# rgb-secamfm500.net
KiCad netlist of a schematic drawn in EAGLE
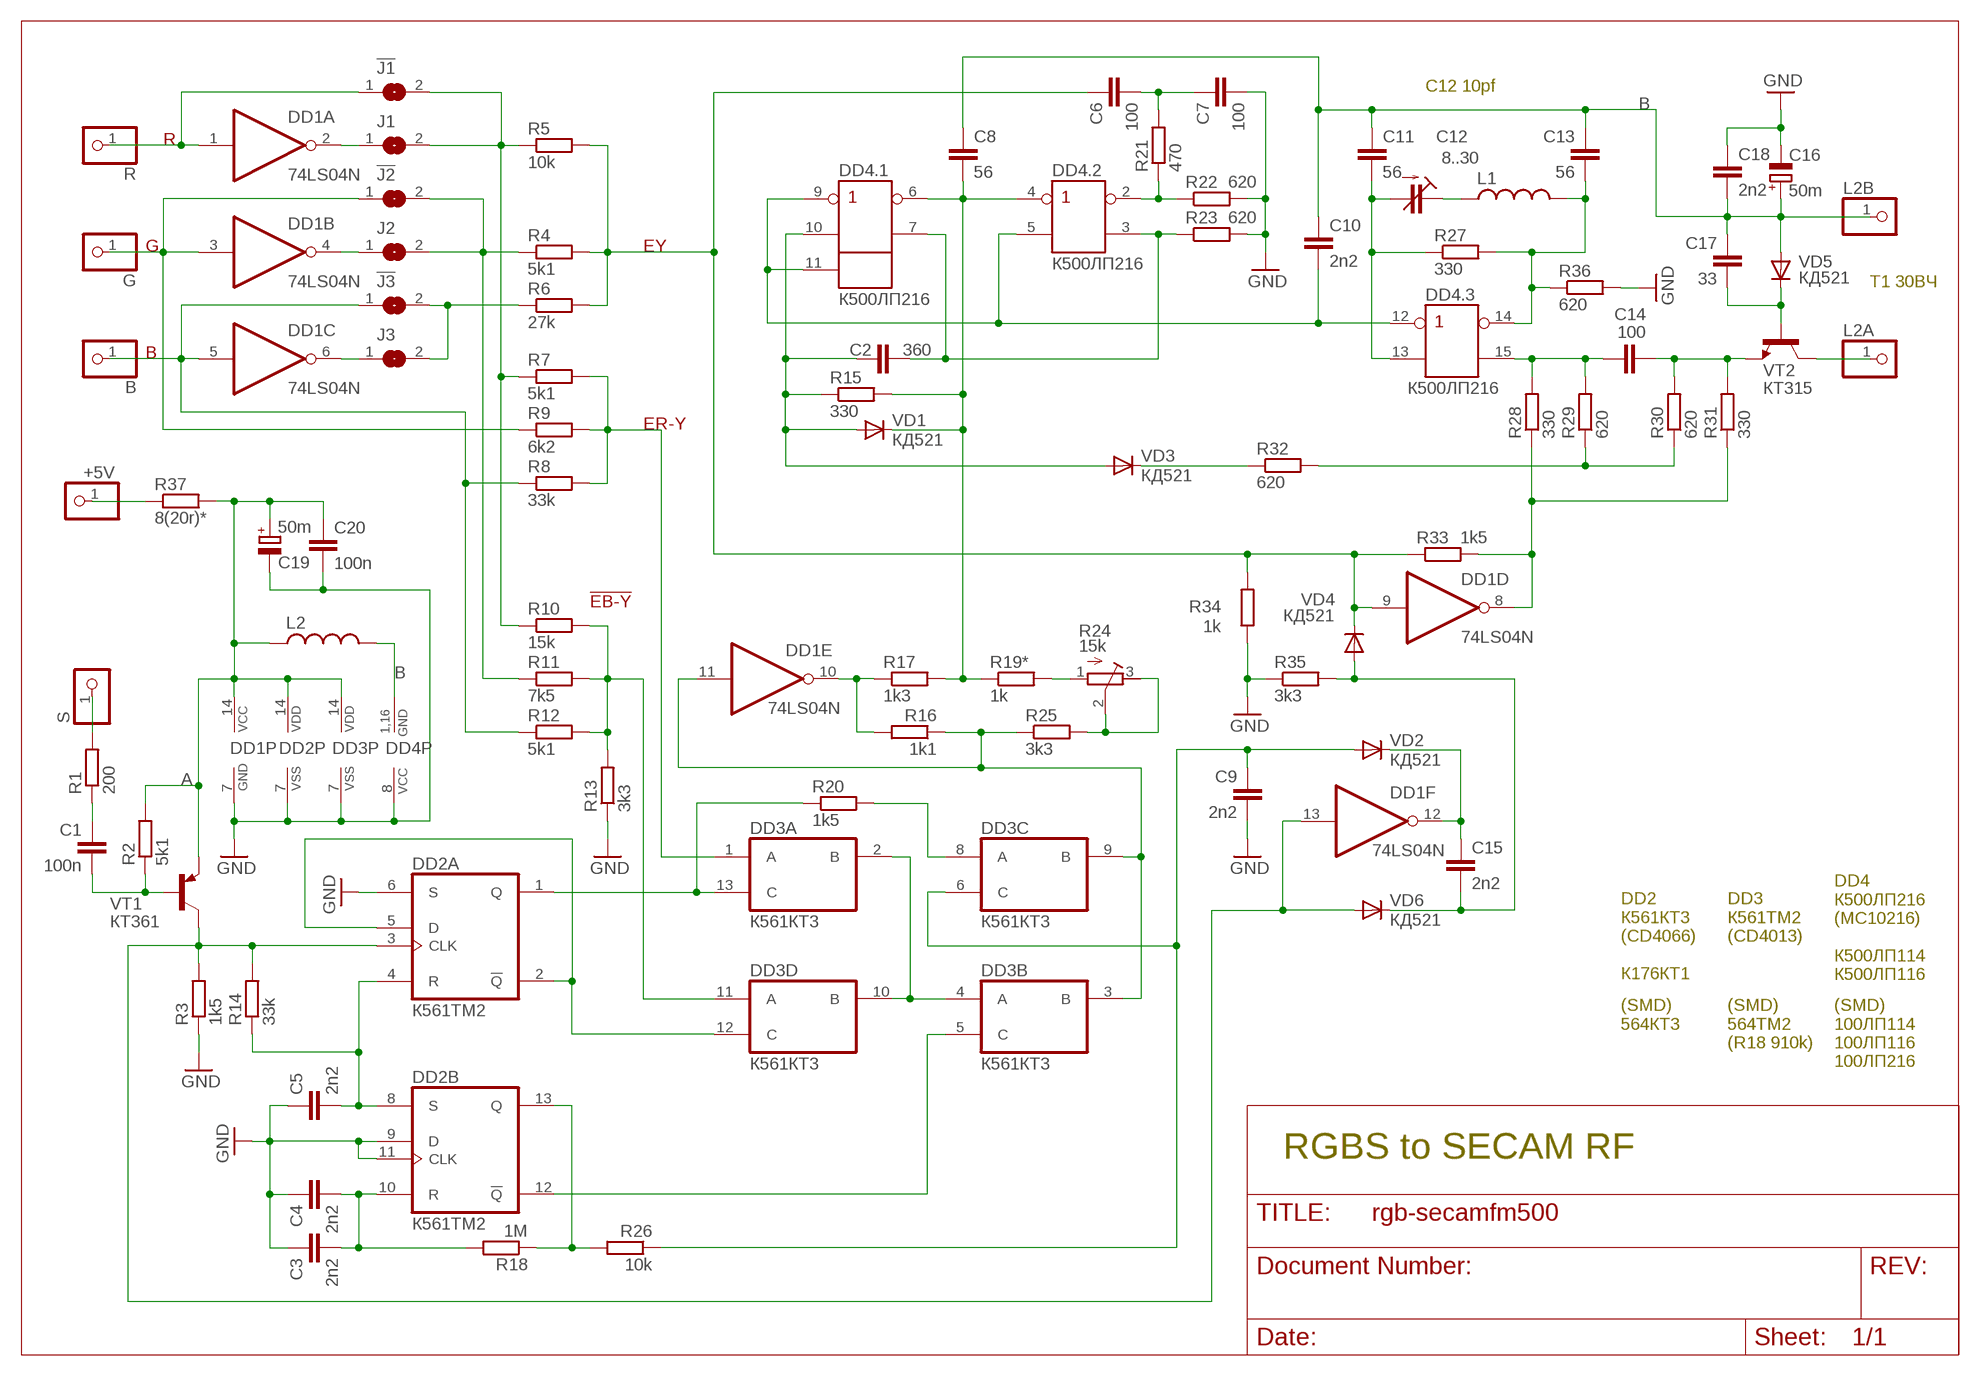
[diagram p0: schematic, sheet 1]

(export (version "E")
  (design (tool "Eeschema 10.0.6"))
  (components
    (comp (ref "!J1") (value "SJ") (footprint "eagle-import:SJ") (libsource (lib "eagle-import") (part "SJ")))
    (comp (ref "!J2") (value "SJ") (footprint "eagle-import:SJ") (libsource (lib "eagle-import") (part "SJ")))
    (comp (ref "!J3") (value "SJ") (footprint "eagle-import:SJ") (libsource (lib "eagle-import") (part "SJ")))
    (comp (ref "+5V")
      (value "PINHD-1X1")
      (footprint "eagle-import:1X01")
      (libsource (lib "eagle-import") (part "PINHD-1X1"))
    )
    (comp (ref "B")
      (value "PINHD-1X1")
      (footprint "eagle-import:1X01")
      (libsource (lib "eagle-import") (part "PINHD-1X1"))
    )
    (comp (ref "C1")
      (value "100n")
      (footprint "eagle-import:C025-025X050")
      (libsource (lib "eagle-import") (part "C-EU025-025X050"))
    )
    (comp (ref "C2")
      (value "360")
      (footprint "eagle-import:C0805K")
      (libsource (lib "eagle-import") (part "C-EUC0805K"))
    )
    (comp (ref "C3")
      (value "2n2")
      (footprint "eagle-import:C0805")
      (libsource (lib "eagle-import") (part "C-EUC0805"))
    )
    (comp (ref "C4")
      (value "2n2")
      (footprint "eagle-import:C0805")
      (libsource (lib "eagle-import") (part "C-EUC0805"))
    )
    (comp (ref "C5")
      (value "2n2")
      (footprint "eagle-import:C0805K")
      (libsource (lib "eagle-import") (part "C-EUC0805K"))
    )
    (comp (ref "C6")
      (value "100")
      (footprint "eagle-import:C0805K")
      (libsource (lib "eagle-import") (part "C-EUC0805K"))
    )
    (comp (ref "C7")
      (value "100")
      (footprint "eagle-import:C0805K")
      (libsource (lib "eagle-import") (part "C-EUC0805K"))
    )
    (comp (ref "C8")
      (value "56")
      (footprint "eagle-import:C0805K")
      (libsource (lib "eagle-import") (part "C-EUC0805K"))
    )
    (comp (ref "C9")
      (value "2n2")
      (footprint "eagle-import:C0805K")
      (libsource (lib "eagle-import") (part "C-EUC0805K"))
    )
    (comp (ref "C10")
      (value "2n2")
      (footprint "eagle-import:C0805K")
      (libsource (lib "eagle-import") (part "C-EUC0805K"))
    )
    (comp (ref "C11")
      (value "56")
      (footprint "eagle-import:C0805K")
      (libsource (lib "eagle-import") (part "C-EUC0805K"))
    )
    (comp (ref "C12")
      (value "8..30")
      (footprint "eagle-import:CTRIM808-1")
      (libsource (lib "eagle-import") (part "C-TRIMM808-1"))
    )
    (comp (ref "C13")
      (value "56")
      (footprint "eagle-import:C0805K")
      (libsource (lib "eagle-import") (part "C-EUC0805K"))
    )
    (comp (ref "C14")
      (value "100")
      (footprint "eagle-import:C0805K")
      (libsource (lib "eagle-import") (part "C-EUC0805K"))
    )
    (comp (ref "C15")
      (value "2n2")
      (footprint "eagle-import:C0805K")
      (libsource (lib "eagle-import") (part "C-EUC0805K"))
    )
    (comp (ref "C16")
      (value "50m")
      (footprint "eagle-import:E2,5-6")
      (libsource (lib "eagle-import") (part "CPOL-EUE2.5-6"))
    )
    (comp (ref "C17")
      (value "33")
      (footprint "eagle-import:C0805K")
      (libsource (lib "eagle-import") (part "C-EUC0805K"))
    )
    (comp (ref "C18")
      (value "2n2")
      (footprint "eagle-import:C0805K")
      (libsource (lib "eagle-import") (part "C-EUC0805K"))
    )
    (comp (ref "C19")
      (value "50m")
      (footprint "eagle-import:E2,5-6")
      (libsource (lib "eagle-import") (part "CPOL-EUE2.5-6"))
    )
    (comp (ref "C20")
      (value "100n")
      (footprint "eagle-import:C0805K")
      (libsource (lib "eagle-import") (part "C-EUC0805K"))
    )
    (comp (ref "DD1")
      (value "74LS04N")
      (footprint "eagle-import:DIL14")
      (libsource (lib "eagle-import") (part "7404NLS"))
    )
    (comp (ref "DD2")
      (value "К561ТМ2")
      (footprint "eagle-import:DIL14")
      (libsource (lib "eagle-import") (part "4013N"))
    )
    (comp (ref "DD3")
      (value "К561КТ3")
      (footprint "eagle-import:DIL14")
      (libsource (lib "eagle-import") (part "4066N"))
    )
    (comp (ref "DD4")
      (value "К500ЛП216")
      (footprint "eagle-import:DIL16B")
      (libsource (lib "eagle-import") (part "К500ЛП216R"))
    )
    (comp (ref "G")
      (value "PINHD-1X1")
      (footprint "eagle-import:1X01")
      (libsource (lib "eagle-import") (part "PINHD-1X1"))
    )
    (comp (ref "J1") (value "SJ") (footprint "eagle-import:SJ") (libsource (lib "eagle-import") (part "SJ")))
    (comp (ref "J2") (value "SJ") (footprint "eagle-import:SJ") (libsource (lib "eagle-import") (part "SJ")))
    (comp (ref "J3") (value "SJ") (footprint "eagle-import:SJ") (libsource (lib "eagle-import") (part "SJ")))
    (comp (ref "L1") (value "L1") (footprint "eagle-import:L1") (libsource (lib "eagle-import") (part "L1")))
    (comp (ref "L2")
      (value "L-US0204/5")
      (footprint "eagle-import:0204_5")
      (libsource (lib "eagle-import") (part "L-US0204/5"))
    )
    (comp (ref "L2A")
      (value "PINHD-1X1")
      (footprint "eagle-import:1X01")
      (libsource (lib "eagle-import") (part "PINHD-1X1"))
    )
    (comp (ref "L2B")
      (value "PINHD-1X1")
      (footprint "eagle-import:1X01")
      (libsource (lib "eagle-import") (part "PINHD-1X1"))
    )
    (comp (ref "R")
      (value "PINHD-1X1")
      (footprint "eagle-import:1X01")
      (libsource (lib "eagle-import") (part "PINHD-1X1"))
    )
    (comp (ref "R1")
      (value "200")
      (footprint "eagle-import:M0805")
      (libsource (lib "eagle-import") (part "R-EU_M0805"))
    )
    (comp (ref "R2")
      (value "5k1")
      (footprint "eagle-import:M0805")
      (libsource (lib "eagle-import") (part "R-EU_M0805"))
    )
    (comp (ref "R3")
      (value "1k5")
      (footprint "eagle-import:M0805")
      (libsource (lib "eagle-import") (part "R-EU_M0805"))
    )
    (comp (ref "R4")
      (value "5k1")
      (footprint "eagle-import:M0805")
      (libsource (lib "eagle-import") (part "R-EU_M0805"))
    )
    (comp (ref "R5")
      (value "10k")
      (footprint "eagle-import:M0805")
      (libsource (lib "eagle-import") (part "R-EU_M0805"))
    )
    (comp (ref "R6")
      (value "27k")
      (footprint "eagle-import:M0805")
      (libsource (lib "eagle-import") (part "R-EU_M0805"))
    )
    (comp (ref "R7")
      (value "5k1")
      (footprint "eagle-import:M0805")
      (libsource (lib "eagle-import") (part "R-EU_M0805"))
    )
    (comp (ref "R8")
      (value "33k")
      (footprint "eagle-import:M0805")
      (libsource (lib "eagle-import") (part "R-EU_M0805"))
    )
    (comp (ref "R9")
      (value "6k2")
      (footprint "eagle-import:M0805")
      (libsource (lib "eagle-import") (part "R-EU_M0805"))
    )
    (comp (ref "R10")
      (value "15k")
      (footprint "eagle-import:M0805")
      (libsource (lib "eagle-import") (part "R-EU_M0805"))
    )
    (comp (ref "R11")
      (value "7k5")
      (footprint "eagle-import:M0805")
      (libsource (lib "eagle-import") (part "R-EU_M0805"))
    )
    (comp (ref "R12")
      (value "5k1")
      (footprint "eagle-import:M0805")
      (libsource (lib "eagle-import") (part "R-EU_M0805"))
    )
    (comp (ref "R13")
      (value "3k3")
      (footprint "eagle-import:M0805")
      (libsource (lib "eagle-import") (part "R-EU_M0805"))
    )
    (comp (ref "R14")
      (value "33k")
      (footprint "eagle-import:M0805")
      (libsource (lib "eagle-import") (part "R-EU_M0805"))
    )
    (comp (ref "R15")
      (value "330")
      (footprint "eagle-import:0207_12")
      (libsource (lib "eagle-import") (part "R-EU_0207/12"))
    )
    (comp (ref "R16")
      (value "1k1")
      (footprint "eagle-import:M0805")
      (libsource (lib "eagle-import") (part "R-EU_M0805"))
    )
    (comp (ref "R17")
      (value "1k3")
      (footprint "eagle-import:M0805")
      (libsource (lib "eagle-import") (part "R-EU_M0805"))
    )
    (comp (ref "R18")
      (value "1M")
      (footprint "eagle-import:M0805")
      (libsource (lib "eagle-import") (part "R-EU_M0805"))
    )
    (comp (ref "R19*")
      (value "1k")
      (footprint "eagle-import:M0805")
      (libsource (lib "eagle-import") (part "R-EU_M0805"))
    )
    (comp (ref "R20")
      (value "1k5")
      (footprint "eagle-import:0207_12")
      (libsource (lib "eagle-import") (part "R-EU_0207/12"))
    )
    (comp (ref "R21")
      (value "470")
      (footprint "eagle-import:M0805")
      (libsource (lib "eagle-import") (part "R-EU_M0805"))
    )
    (comp (ref "R22")
      (value "620")
      (footprint "eagle-import:M0805")
      (libsource (lib "eagle-import") (part "R-EU_M0805"))
    )
    (comp (ref "R23")
      (value "620")
      (footprint "eagle-import:M0805")
      (libsource (lib "eagle-import") (part "R-EU_M0805"))
    )
    (comp (ref "R24")
      (value "15k")
      (footprint "eagle-import:RTRIM3296W")
      (libsource (lib "eagle-import") (part "R-TRIMM3296W"))
    )
    (comp (ref "R25")
      (value "3k3")
      (footprint "eagle-import:M0805")
      (libsource (lib "eagle-import") (part "R-EU_M0805"))
    )
    (comp (ref "R26")
      (value "10k")
      (footprint "eagle-import:M0805")
      (libsource (lib "eagle-import") (part "R-EU_M0805"))
    )
    (comp (ref "R27")
      (value "330")
      (footprint "eagle-import:M0805")
      (libsource (lib "eagle-import") (part "R-EU_M0805"))
    )
    (comp (ref "R28")
      (value "330")
      (footprint "eagle-import:M0805")
      (libsource (lib "eagle-import") (part "R-EU_M0805"))
    )
    (comp (ref "R29")
      (value "620")
      (footprint "eagle-import:M0805")
      (libsource (lib "eagle-import") (part "R-EU_M0805"))
    )
    (comp (ref "R30")
      (value "620")
      (footprint "eagle-import:M0805")
      (libsource (lib "eagle-import") (part "R-EU_M0805"))
    )
    (comp (ref "R31")
      (value "330")
      (footprint "eagle-import:M0805")
      (libsource (lib "eagle-import") (part "R-EU_M0805"))
    )
    (comp (ref "R32")
      (value "620")
      (footprint "eagle-import:M0805")
      (libsource (lib "eagle-import") (part "R-EU_M0805"))
    )
    (comp (ref "R33")
      (value "1k5")
      (footprint "eagle-import:M0805")
      (libsource (lib "eagle-import") (part "R-EU_M0805"))
    )
    (comp (ref "R34")
      (value "1k")
      (footprint "eagle-import:M0805")
      (libsource (lib "eagle-import") (part "R-EU_M0805"))
    )
    (comp (ref "R35")
      (value "3k3")
      (footprint "eagle-import:M0805")
      (libsource (lib "eagle-import") (part "R-EU_M0805"))
    )
    (comp (ref "R36")
      (value "620")
      (footprint "eagle-import:M0805")
      (libsource (lib "eagle-import") (part "R-EU_M0805"))
    )
    (comp (ref "R37")
      (value "8(20r)*")
      (footprint "eagle-import:R1210")
      (libsource (lib "eagle-import") (part "R-EU_R1210"))
    )
    (comp (ref "S")
      (value "PINHD-1X1")
      (footprint "eagle-import:1X01")
      (libsource (lib "eagle-import") (part "PINHD-1X1"))
    )
    (comp (ref "VD1")
      (value "КД521")
      (footprint "eagle-import:D-7.5")
      (libsource (lib "eagle-import") (part "DIODE-D-7.5"))
    )
    (comp (ref "VD2")
      (value "КД521")
      (footprint "eagle-import:D-7.5")
      (libsource (lib "eagle-import") (part "DIODE-D-7.5"))
    )
    (comp (ref "VD3")
      (value "КД521")
      (footprint "eagle-import:D-7.5")
      (libsource (lib "eagle-import") (part "DIODE-D-7.5"))
    )
    (comp (ref "VD4")
      (value "КД521")
      (footprint "eagle-import:D-7.5")
      (libsource (lib "eagle-import") (part "DIODE-D-7.5"))
    )
    (comp (ref "VD5")
      (value "КД521")
      (footprint "eagle-import:D-7.5")
      (libsource (lib "eagle-import") (part "DIODE-D-7.5"))
    )
    (comp (ref "VD6")
      (value "КД521")
      (footprint "eagle-import:D-7.5")
      (libsource (lib "eagle-import") (part "DIODE-D-7.5"))
    )
    (comp (ref "VT1")
      (value "КТ361")
      (footprint "eagle-import:TO92")
      (libsource (lib "eagle-import") (part "BJT_PNP_TO-92_ECB"))
    )
    (comp (ref "VT2")
      (value "КТ315")
      (footprint "eagle-import:TO92")
      (libsource (lib "eagle-import") (part "BJT_NPN_TO-92_ECB"))
    )
  )
  (nets
    (net (code "1") (name "/A") (class "Default")
      (node (ref "C19") (pin "+") (pinfunction "+_+") (pintype "passive"))
      (node (ref "C20") (pin "1") (pinfunction "1_1") (pintype "passive"))
      (node (ref "DD1") (pin "14") (pinfunction "VCC_14") (pintype "power_in"))
      (node (ref "DD2") (pin "14") (pinfunction "VDD_14") (pintype "power_in"))
      (node (ref "DD3") (pin "14") (pinfunction "VDD_14") (pintype "power_in"))
      (node (ref "L2") (pin "1") (pinfunction "1_1") (pintype "passive"))
      (node (ref "R2") (pin "2") (pinfunction "2_2") (pintype "passive"))
      (node (ref "R37") (pin "2") (pinfunction "2_2") (pintype "passive"))
      (node (ref "VT1") (pin "1") (pinfunction "E_1") (pintype "passive"))
    )
    (net (code "2") (name "/B") (class "Default")
      (node (ref "C10") (pin "1") (pinfunction "1_1") (pintype "passive"))
      (node (ref "C11") (pin "1") (pinfunction "1_1") (pintype "passive"))
      (node (ref "C13") (pin "1") (pinfunction "1_1") (pintype "passive"))
      (node (ref "C16") (pin "+") (pinfunction "+_+") (pintype "passive"))
      (node (ref "C17") (pin "1") (pinfunction "1_1") (pintype "passive"))
      (node (ref "C18") (pin "2") (pinfunction "2_2") (pintype "passive"))
      (node (ref "C8") (pin "1") (pinfunction "1_1") (pintype "passive"))
      (node (ref "DD4") (pin "1") (pinfunction "GND_1") (pintype "power_in"))
      (node (ref "DD4") (pin "16") (pinfunction "GND_16") (pintype "power_in"))
      (node (ref "L2") (pin "2") (pinfunction "2_2") (pintype "passive"))
      (node (ref "L2B") (pin "1") (pinfunction "1_1") (pintype "passive"))
      (node (ref "VD5") (pin "A") (pinfunction "A_A") (pintype "passive"))
    )
    (net (code "3") (name "GND") (class "Default")
      (node (ref "C16") (pin "-") (pinfunction "-_-") (pintype "passive"))
      (node (ref "C18") (pin "1") (pinfunction "1_1") (pintype "passive"))
      (node (ref "C19") (pin "-") (pinfunction "-_-") (pintype "passive"))
      (node (ref "C20") (pin "2") (pinfunction "2_2") (pintype "passive"))
      (node (ref "C3") (pin "1") (pinfunction "1_1") (pintype "passive"))
      (node (ref "C4") (pin "1") (pinfunction "1_1") (pintype "passive"))
      (node (ref "C5") (pin "1") (pinfunction "1_1") (pintype "passive"))
      (node (ref "C7") (pin "2") (pinfunction "2_2") (pintype "passive"))
      (node (ref "C9") (pin "2") (pinfunction "2_2") (pintype "passive"))
      (node (ref "DD1") (pin "7") (pinfunction "GND_7") (pintype "power_in"))
      (node (ref "DD2") (pin "11") (pinfunction "CLK_11") (pintype "input"))
      (node (ref "DD2") (pin "6") (pinfunction "S_6") (pintype "input"))
      (node (ref "DD2") (pin "7") (pinfunction "VSS_7") (pintype "power_in"))
      (node (ref "DD2") (pin "9") (pinfunction "D_9") (pintype "input"))
      (node (ref "DD3") (pin "7") (pinfunction "VSS_7") (pintype "power_in"))
      (node (ref "DD4") (pin "8") (pinfunction "VCC_8") (pintype "power_in"))
      (node (ref "R13") (pin "1") (pinfunction "1_1") (pintype "passive"))
      (node (ref "R22") (pin "2") (pinfunction "2_2") (pintype "passive"))
      (node (ref "R23") (pin "2") (pinfunction "2_2") (pintype "passive"))
      (node (ref "R3") (pin "1") (pinfunction "1_1") (pintype "passive"))
      (node (ref "R34") (pin "1") (pinfunction "1_1") (pintype "passive"))
      (node (ref "R35") (pin "1") (pinfunction "1_1") (pintype "passive"))
      (node (ref "R36") (pin "2") (pinfunction "2_2") (pintype "passive"))
    )
    (net (code "4") (name "Net-(!J1-Pad2)") (class "Default")
      (node (ref "!J1") (pin "2") (pinfunction "2_2") (pintype "passive"))
      (node (ref "J1") (pin "2") (pinfunction "2_2") (pintype "passive"))
      (node (ref "R10") (pin "1") (pinfunction "1_1") (pintype "passive"))
      (node (ref "R5") (pin "1") (pinfunction "1_1") (pintype "passive"))
      (node (ref "R7") (pin "1") (pinfunction "1_1") (pintype "passive"))
    )
    (net (code "5") (name "Net-(!J2-Pad2)") (class "Default")
      (node (ref "!J2") (pin "2") (pinfunction "2_2") (pintype "passive"))
      (node (ref "J2") (pin "2") (pinfunction "2_2") (pintype "passive"))
      (node (ref "R11") (pin "1") (pinfunction "1_1") (pintype "passive"))
      (node (ref "R4") (pin "1") (pinfunction "1_1") (pintype "passive"))
    )
    (net (code "6") (name "Net-(!J3-Pad2)") (class "Default")
      (node (ref "!J3") (pin "2") (pinfunction "2_2") (pintype "passive"))
      (node (ref "J3") (pin "2") (pinfunction "2_2") (pintype "passive"))
      (node (ref "R6") (pin "1") (pinfunction "1_1") (pintype "passive"))
    )
    (net (code "7") (name "Net-(+5V-Pad1)") (class "Default")
      (node (ref "+5V") (pin "1") (pinfunction "1_1") (pintype "passive"))
      (node (ref "R37") (pin "1") (pinfunction "1_1") (pintype "passive"))
    )
    (net (code "8") (name "Net-(C1-Pad1)") (class "Default")
      (node (ref "C1") (pin "1") (pinfunction "1_1") (pintype "passive"))
      (node (ref "R1") (pin "1") (pinfunction "1_1") (pintype "passive"))
    )
    (net (code "9") (name "Net-(C6-Pad2)") (class "Default")
      (node (ref "C6") (pin "2") (pinfunction "2_2") (pintype "passive"))
      (node (ref "C7") (pin "1") (pinfunction "1_1") (pintype "passive"))
      (node (ref "R21") (pin "2") (pinfunction "2_2") (pintype "passive"))
    )
    (net (code "10") (name "Net-(C12-A)") (class "Default")
      (node (ref "C11") (pin "2") (pinfunction "2_2") (pintype "passive"))
      (node (ref "C12") (pin "2") (pinfunction "A_2") (pintype "passive"))
      (node (ref "DD4") (pin "13") (pinfunction "IN_13") (pintype "input"))
      (node (ref "R27") (pin "1") (pinfunction "1_1") (pintype "passive"))
    )
    (net (code "11") (name "Net-(C12-E)") (class "Default")
      (node (ref "C12") (pin "1") (pinfunction "E_1") (pintype "passive"))
      (node (ref "L1") (pin "P$1") (pinfunction "1_P$1") (pintype "passive"))
    )
    (net (code "12") (name "Net-(C15-Pad2)") (class "Default")
      (node (ref "C15") (pin "2") (pinfunction "2_2") (pintype "passive"))
      (node (ref "R35") (pin "2") (pinfunction "2_2") (pintype "passive"))
      (node (ref "VD4") (pin "A") (pinfunction "A_A") (pintype "passive"))
      (node (ref "VD6") (pin "C") (pinfunction "C_C") (pintype "passive"))
    )
    (net (code "13") (name "Net-(DD1A-I)") (class "Default")
      (node (ref "!J1") (pin "1") (pinfunction "1_1") (pintype "passive"))
      (node (ref "DD1") (pin "1") (pinfunction "I_1") (pintype "input"))
      (node (ref "R") (pin "1") (pinfunction "1_1") (pintype "passive"))
    )
    (net (code "14") (name "Net-(DD1A-O)") (class "Default")
      (node (ref "DD1") (pin "2") (pinfunction "O_2") (pintype "output"))
      (node (ref "J1") (pin "1") (pinfunction "1_1") (pintype "passive"))
    )
    (net (code "15") (name "Net-(DD1B-I)") (class "Default")
      (node (ref "!J2") (pin "1") (pinfunction "1_1") (pintype "passive"))
      (node (ref "DD1") (pin "3") (pinfunction "I_3") (pintype "input"))
      (node (ref "G") (pin "1") (pinfunction "1_1") (pintype "passive"))
      (node (ref "R9") (pin "1") (pinfunction "1_1") (pintype "passive"))
    )
    (net (code "16") (name "Net-(DD1B-O)") (class "Default")
      (node (ref "DD1") (pin "4") (pinfunction "O_4") (pintype "output"))
      (node (ref "J2") (pin "1") (pinfunction "1_1") (pintype "passive"))
    )
    (net (code "17") (name "Net-(DD1C-I)") (class "Default")
      (node (ref "!J3") (pin "1") (pinfunction "1_1") (pintype "passive"))
      (node (ref "B") (pin "1") (pinfunction "1_1") (pintype "passive"))
      (node (ref "DD1") (pin "5") (pinfunction "I_5") (pintype "input"))
      (node (ref "R12") (pin "1") (pinfunction "1_1") (pintype "passive"))
      (node (ref "R8") (pin "1") (pinfunction "1_1") (pintype "passive"))
    )
    (net (code "18") (name "Net-(DD1C-O)") (class "Default")
      (node (ref "DD1") (pin "6") (pinfunction "O_6") (pintype "output"))
      (node (ref "J3") (pin "1") (pinfunction "1_1") (pintype "passive"))
    )
    (net (code "19") (name "Net-(DD1D-I)") (class "Default")
      (node (ref "C6") (pin "1") (pinfunction "1_1") (pintype "passive"))
      (node (ref "DD1") (pin "9") (pinfunction "I_9") (pintype "input"))
      (node (ref "R33") (pin "1") (pinfunction "1_1") (pintype "passive"))
      (node (ref "R34") (pin "2") (pinfunction "2_2") (pintype "passive"))
      (node (ref "R4") (pin "2") (pinfunction "2_2") (pintype "passive"))
      (node (ref "R5") (pin "2") (pinfunction "2_2") (pintype "passive"))
      (node (ref "R6") (pin "2") (pinfunction "2_2") (pintype "passive"))
      (node (ref "VD4") (pin "C") (pinfunction "C_C") (pintype "passive"))
    )
    (net (code "20") (name "Net-(DD1D-O)") (class "Default")
      (node (ref "DD1") (pin "8") (pinfunction "O_8") (pintype "output"))
      (node (ref "R28") (pin "1") (pinfunction "1_1") (pintype "passive"))
      (node (ref "R31") (pin "1") (pinfunction "1_1") (pintype "passive"))
      (node (ref "R33") (pin "2") (pinfunction "2_2") (pintype "passive"))
    )
    (net (code "21") (name "Net-(DD1E-I)") (class "Default")
      (node (ref "DD1") (pin "11") (pinfunction "I_11") (pintype "input"))
      (node (ref "DD3") (pin "3") (pinfunction "B_3") (pintype "tri_state"))
      (node (ref "DD3") (pin "9") (pinfunction "B_9") (pintype "tri_state"))
      (node (ref "R16") (pin "1") (pinfunction "1_1") (pintype "passive"))
      (node (ref "R25") (pin "1") (pinfunction "1_1") (pintype "passive"))
    )
    (net (code "22") (name "Net-(DD1E-O)") (class "Default")
      (node (ref "DD1") (pin "10") (pinfunction "O_10") (pintype "output"))
      (node (ref "R16") (pin "2") (pinfunction "2_2") (pintype "passive"))
      (node (ref "R17") (pin "1") (pinfunction "1_1") (pintype "passive"))
    )
    (net (code "23") (name "Net-(DD1F-I)") (class "Default")
      (node (ref "DD1") (pin "13") (pinfunction "I_13") (pintype "input"))
      (node (ref "DD2") (pin "3") (pinfunction "CLK_3") (pintype "input"))
      (node (ref "R14") (pin "2") (pinfunction "2_2") (pintype "passive"))
      (node (ref "R3") (pin "2") (pinfunction "2_2") (pintype "passive"))
      (node (ref "VD6") (pin "A") (pinfunction "A_A") (pintype "passive"))
      (node (ref "VT1") (pin "2") (pinfunction "C_2") (pintype "passive"))
    )
    (net (code "24") (name "Net-(DD1F-O)") (class "Default")
      (node (ref "C15") (pin "1") (pinfunction "1_1") (pintype "passive"))
      (node (ref "DD1") (pin "12") (pinfunction "O_12") (pintype "output"))
      (node (ref "VD2") (pin "C") (pinfunction "C_C") (pintype "passive"))
    )
    (net (code "25") (name "Net-(DD2A-D)") (class "Default")
      (node (ref "DD2") (pin "2") (pinfunction "~{Q}_2") (pintype "output"))
      (node (ref "DD2") (pin "5") (pinfunction "D_5") (pintype "input"))
      (node (ref "DD3") (pin "12") (pinfunction "C_12") (pintype "input"))
    )
    (net (code "26") (name "Net-(DD2A-Q)") (class "Default")
      (node (ref "DD2") (pin "1") (pinfunction "Q_1") (pintype "output"))
      (node (ref "DD3") (pin "13") (pinfunction "C_13") (pintype "input"))
      (node (ref "R20") (pin "1") (pinfunction "1_1") (pintype "passive"))
    )
    (net (code "27") (name "Net-(DD2A-R)") (class "Default")
      (node (ref "C5") (pin "2") (pinfunction "2_2") (pintype "passive"))
      (node (ref "DD2") (pin "4") (pinfunction "R_4") (pintype "input"))
      (node (ref "DD2") (pin "8") (pinfunction "S_8") (pintype "input"))
      (node (ref "R14") (pin "1") (pinfunction "1_1") (pintype "passive"))
    )
    (net (code "28") (name "Net-(DD2B-Q)") (class "Default")
      (node (ref "DD2") (pin "13") (pinfunction "Q_13") (pintype "output"))
      (node (ref "R18") (pin "1") (pinfunction "1_1") (pintype "passive"))
      (node (ref "R26") (pin "2") (pinfunction "2_2") (pintype "passive"))
    )
    (net (code "29") (name "Net-(DD2B-R)") (class "Default")
      (node (ref "C3") (pin "2") (pinfunction "2_2") (pintype "passive"))
      (node (ref "C4") (pin "2") (pinfunction "2_2") (pintype "passive"))
      (node (ref "DD2") (pin "10") (pinfunction "R_10") (pintype "input"))
      (node (ref "R18") (pin "2") (pinfunction "2_2") (pintype "passive"))
    )
    (net (code "30") (name "Net-(DD2B-~{Q})") (class "Default")
      (node (ref "DD2") (pin "12") (pinfunction "~{Q}_12") (pintype "output"))
      (node (ref "DD3") (pin "5") (pinfunction "C_5") (pintype "input"))
    )
    (net (code "31") (name "Net-(DD3A-A)") (class "Default")
      (node (ref "DD3") (pin "1") (pinfunction "A_1") (pintype "tri_state"))
      (node (ref "R7") (pin "2") (pinfunction "2_2") (pintype "passive"))
      (node (ref "R8") (pin "2") (pinfunction "2_2") (pintype "passive"))
      (node (ref "R9") (pin "2") (pinfunction "2_2") (pintype "passive"))
    )
    (net (code "32") (name "Net-(DD3A-B)") (class "Default")
      (node (ref "DD3") (pin "10") (pinfunction "B_10") (pintype "tri_state"))
      (node (ref "DD3") (pin "2") (pinfunction "B_2") (pintype "tri_state"))
      (node (ref "DD3") (pin "4") (pinfunction "A_4") (pintype "tri_state"))
    )
    (net (code "33") (name "Net-(DD3C-A)") (class "Default")
      (node (ref "DD3") (pin "8") (pinfunction "A_8") (pintype "tri_state"))
      (node (ref "R20") (pin "2") (pinfunction "2_2") (pintype "passive"))
    )
    (net (code "34") (name "Net-(DD3C-C)") (class "Default")
      (node (ref "C9") (pin "1") (pinfunction "1_1") (pintype "passive"))
      (node (ref "DD3") (pin "6") (pinfunction "C_6") (pintype "input"))
      (node (ref "R26") (pin "1") (pinfunction "1_1") (pintype "passive"))
      (node (ref "VD2") (pin "A") (pinfunction "A_A") (pintype "passive"))
    )
    (net (code "35") (name "Net-(DD3D-A)") (class "Default")
      (node (ref "DD3") (pin "11") (pinfunction "A_11") (pintype "tri_state"))
      (node (ref "R10") (pin "2") (pinfunction "2_2") (pintype "passive"))
      (node (ref "R11") (pin "2") (pinfunction "2_2") (pintype "passive"))
      (node (ref "R12") (pin "2") (pinfunction "2_2") (pintype "passive"))
      (node (ref "R13") (pin "2") (pinfunction "2_2") (pintype "passive"))
    )
    (net (code "36") (name "Net-(DD4A-IN)") (class "Default")
      (node (ref "C2") (pin "1") (pinfunction "1_1") (pintype "passive"))
      (node (ref "DD4") (pin "10") (pinfunction "IN_10") (pintype "input"))
      (node (ref "R15") (pin "1") (pinfunction "1_1") (pintype "passive"))
      (node (ref "VD1") (pin "A") (pinfunction "A_A") (pintype "passive"))
      (node (ref "VD3") (pin "A") (pinfunction "A_A") (pintype "passive"))
    )
    (net (code "37") (name "Net-(DD4A-OUT)") (class "Default")
      (node (ref "C2") (pin "2") (pinfunction "2_2") (pintype "passive"))
      (node (ref "DD4") (pin "3") (pinfunction "OUT_3") (pintype "output"))
      (node (ref "DD4") (pin "7") (pinfunction "OUT_7") (pintype "output"))
      (node (ref "R23") (pin "1") (pinfunction "1_1") (pintype "passive"))
    )
    (net (code "38") (name "Net-(DD4A-V)") (class "Default")
      (node (ref "C10") (pin "2") (pinfunction "2_2") (pintype "passive"))
      (node (ref "DD4") (pin "11") (pinfunction "V_11") (pintype "input"))
      (node (ref "DD4") (pin "12") (pinfunction "~{IN}_12") (pintype "input"))
      (node (ref "DD4") (pin "5") (pinfunction "IN_5") (pintype "input"))
      (node (ref "DD4") (pin "9") (pinfunction "~{IN}_9") (pintype "input"))
    )
    (net (code "39") (name "Net-(DD4A-~{OUT})") (class "Default")
      (node (ref "C8") (pin "2") (pinfunction "2_2") (pintype "passive"))
      (node (ref "DD4") (pin "4") (pinfunction "~{IN}_4") (pintype "input"))
      (node (ref "DD4") (pin "6") (pinfunction "~{OUT}_6") (pintype "output"))
      (node (ref "R15") (pin "2") (pinfunction "2_2") (pintype "passive"))
      (node (ref "R17") (pin "2") (pinfunction "2_2") (pintype "passive"))
      (node (ref "R19*") (pin "1") (pinfunction "1_1") (pintype "passive"))
      (node (ref "VD1") (pin "C") (pinfunction "C_C") (pintype "passive"))
    )
    (net (code "40") (name "Net-(DD4B-~{OUT})") (class "Default")
      (node (ref "DD4") (pin "2") (pinfunction "~{OUT}_2") (pintype "output"))
      (node (ref "R21") (pin "1") (pinfunction "1_1") (pintype "passive"))
      (node (ref "R22") (pin "1") (pinfunction "1_1") (pintype "passive"))
    )
    (net (code "41") (name "Net-(DD4C-OUT)") (class "Default")
      (node (ref "C14") (pin "1") (pinfunction "1_1") (pintype "passive"))
      (node (ref "DD4") (pin "15") (pinfunction "OUT_15") (pintype "output"))
      (node (ref "R28") (pin "2") (pinfunction "2_2") (pintype "passive"))
      (node (ref "R29") (pin "2") (pinfunction "2_2") (pintype "passive"))
    )
    (net (code "42") (name "Net-(DD4C-~{OUT})") (class "Default")
      (node (ref "C13") (pin "2") (pinfunction "2_2") (pintype "passive"))
      (node (ref "DD4") (pin "14") (pinfunction "~{OUT}_14") (pintype "output"))
      (node (ref "L1") (pin "P$2") (pinfunction "2_P$2") (pintype "passive"))
      (node (ref "R27") (pin "2") (pinfunction "2_2") (pintype "passive"))
      (node (ref "R36") (pin "1") (pinfunction "1_1") (pintype "passive"))
    )
    (net (code "43") (name "Net-(R1-Pad2)") (class "Default")
      (node (ref "R1") (pin "2") (pinfunction "2_2") (pintype "passive"))
      (node (ref "S") (pin "1") (pinfunction "1_1") (pintype "passive"))
    )
    (net (code "44") (name "Net-(R24-A)") (class "Default")
      (node (ref "R19*") (pin "2") (pinfunction "2_2") (pintype "passive"))
      (node (ref "R24") (pin "1") (pinfunction "A_1") (pintype "passive"))
    )
    (net (code "45") (name "Net-(R24-E)") (class "Default")
      (node (ref "R24") (pin "2") (pinfunction "S_2") (pintype "passive"))
      (node (ref "R24") (pin "3") (pinfunction "E_3") (pintype "passive"))
      (node (ref "R25") (pin "2") (pinfunction "2_2") (pintype "passive"))
    )
    (net (code "46") (name "Net-(R29-Pad1)") (class "Default")
      (node (ref "R29") (pin "1") (pinfunction "1_1") (pintype "passive"))
      (node (ref "R30") (pin "1") (pinfunction "1_1") (pintype "passive"))
      (node (ref "R32") (pin "2") (pinfunction "2_2") (pintype "passive"))
    )
    (net (code "47") (name "Net-(R32-Pad1)") (class "Default")
      (node (ref "R32") (pin "1") (pinfunction "1_1") (pintype "passive"))
      (node (ref "VD3") (pin "C") (pinfunction "C_C") (pintype "passive"))
    )
    (net (code "48") (name "Net-(VT1-B)") (class "Default")
      (node (ref "C1") (pin "2") (pinfunction "2_2") (pintype "passive"))
      (node (ref "R2") (pin "1") (pinfunction "1_1") (pintype "passive"))
      (node (ref "VT1") (pin "3") (pinfunction "B_3") (pintype "passive"))
    )
    (net (code "49") (name "Net-(VT2-B)") (class "Default")
      (node (ref "C17") (pin "2") (pinfunction "2_2") (pintype "passive"))
      (node (ref "VD5") (pin "C") (pinfunction "C_C") (pintype "passive"))
      (node (ref "VT2") (pin "3") (pinfunction "B_3") (pintype "passive"))
    )
    (net (code "50") (name "Net-(VT2-C)") (class "Default")
      (node (ref "L2A") (pin "1") (pinfunction "1_1") (pintype "passive"))
      (node (ref "VT2") (pin "2") (pinfunction "C_2") (pintype "passive"))
    )
    (net (code "51") (name "Net-(VT2-E)") (class "Default")
      (node (ref "C14") (pin "2") (pinfunction "2_2") (pintype "passive"))
      (node (ref "R30") (pin "2") (pinfunction "2_2") (pintype "passive"))
      (node (ref "R31") (pin "2") (pinfunction "2_2") (pintype "passive"))
      (node (ref "VT2") (pin "1") (pinfunction "E_1") (pintype "passive"))
    )
  )
)
